# Spectacle_Motion_Board.net
KiCad netlist of a schematic drawn in EAGLE
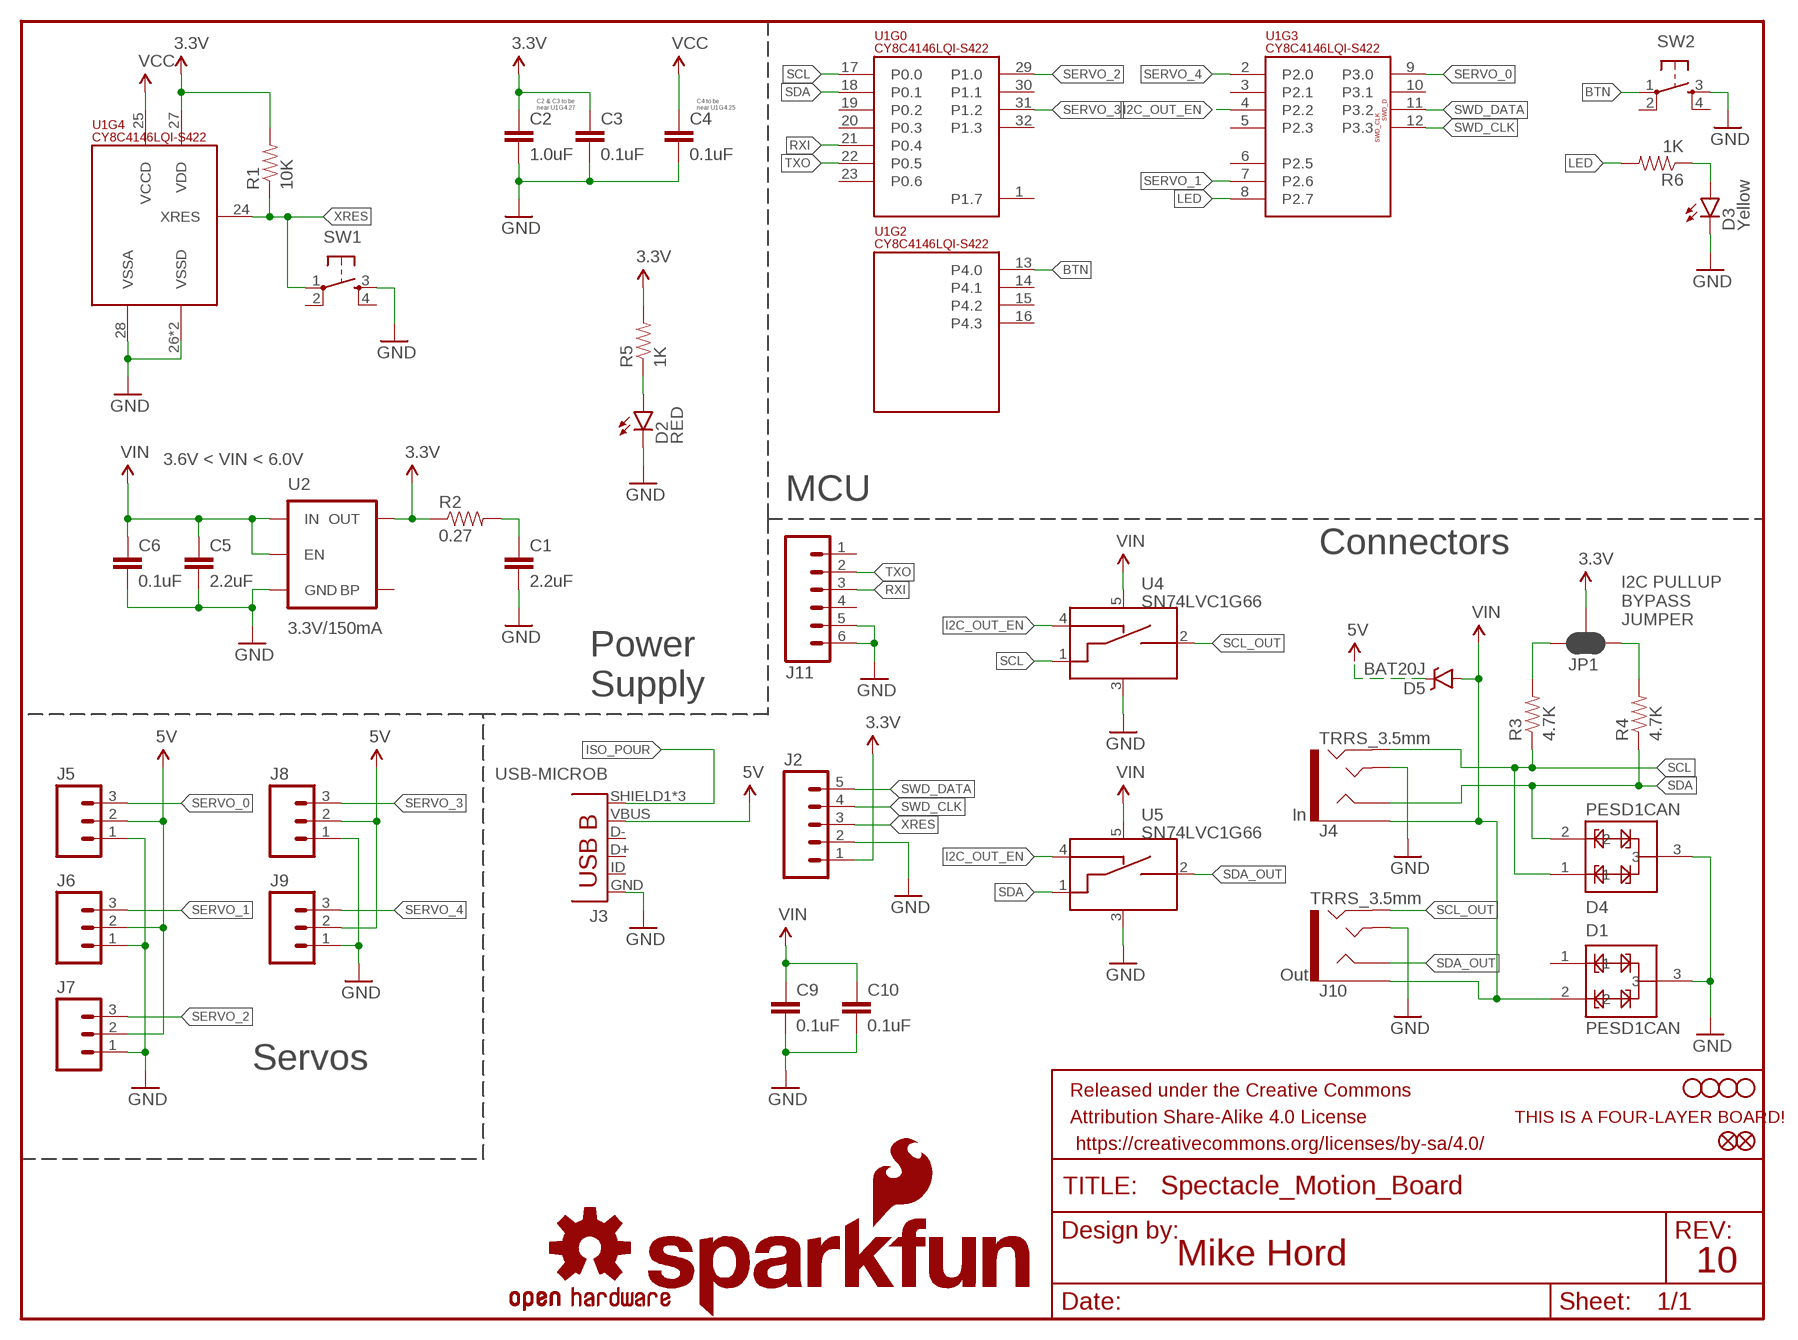
[diagram p0: schematic, sheet 1]

(export (version "E")
  (design (tool "Eeschema 10.0.6"))
  (components
    (comp (ref "C1")
      (value "2.2uF")
      (footprint "eagle-import:0603-CAP")
      (libsource (lib "eagle-import") (part "2.2UF-10V-20%(0603)"))
    )
    (comp (ref "C2")
      (value "1.0uF")
      (footprint "eagle-import:0402-CAP")
      (libsource (lib "eagle-import") (part "1.0UF-16V-10%(0402)"))
    )
    (comp (ref "C3")
      (value "0.1uF")
      (footprint "eagle-import:0402-CAP")
      (libsource (lib "eagle-import") (part "0.1UF-16V(+-10%)(0402)"))
    )
    (comp (ref "C4")
      (value "0.1uF")
      (footprint "eagle-import:0402-CAP")
      (libsource (lib "eagle-import") (part "0.1UF-16V(+-10%)(0402)"))
    )
    (comp (ref "C5")
      (value "2.2uF")
      (footprint "eagle-import:0603-CAP")
      (libsource (lib "eagle-import") (part "2.2UF-10V-20%(0603)"))
    )
    (comp (ref "C6")
      (value "0.1uF")
      (footprint "eagle-import:0402-CAP")
      (libsource (lib "eagle-import") (part "0.1UF-16V(+-10%)(0402)"))
    )
    (comp (ref "C9")
      (value "0.1uF")
      (footprint "eagle-import:0402-CAP")
      (libsource (lib "eagle-import") (part "0.1UF-16V(+-10%)(0402)"))
    )
    (comp (ref "C10")
      (value "0.1uF")
      (footprint "eagle-import:0402-CAP")
      (libsource (lib "eagle-import") (part "0.1UF-16V(+-10%)(0402)"))
    )
    (comp (ref "D1")
      (value "PESD1CAN")
      (footprint "eagle-import:SOT23-3")
      (libsource (lib "eagle-import") (part "PESD1CAN"))
    )
    (comp (ref "D2")
      (value "RED")
      (footprint "eagle-import:LED-0603")
      (libsource (lib "eagle-import") (part "LED-RED0603"))
    )
    (comp (ref "D3")
      (value "Yellow")
      (footprint "eagle-import:LED-0603")
      (libsource (lib "eagle-import") (part "LED-YELLOW0603-SMART"))
    )
    (comp (ref "D4")
      (value "PESD1CAN")
      (footprint "eagle-import:SOT23-3")
      (libsource (lib "eagle-import") (part "PESD1CAN"))
    )
    (comp (ref "D5")
      (value "BAT20J")
      (footprint "eagle-import:SOD-323")
      (libsource (lib "eagle-import") (part "DIODE-SCHOTTKY-BAT20J"))
    )
    (comp (ref "FD1")
      (value "FIDUCIALUFIDUCIAL")
      (footprint "eagle-import:MICRO-FIDUCIAL")
      (libsource (lib "eagle-import") (part "FIDUCIALUFIDUCIAL"))
    )
    (comp (ref "FD2")
      (value "FIDUCIALUFIDUCIAL")
      (footprint "eagle-import:MICRO-FIDUCIAL")
      (libsource (lib "eagle-import") (part "FIDUCIALUFIDUCIAL"))
    )
    (comp (ref "FRAME1")
      (value "FRAME-LETTER")
      (footprint "eagle-import:CREATIVE_COMMONS")
      (libsource (lib "eagle-import") (part "FRAME-LETTER"))
    )
    (comp (ref "H1")
      (value "STAND-OFF")
      (footprint "eagle-import:STAND-OFF")
      (libsource (lib "eagle-import") (part "STAND-OFF"))
    )
    (comp (ref "H2")
      (value "STAND-OFF")
      (footprint "eagle-import:STAND-OFF")
      (libsource (lib "eagle-import") (part "STAND-OFF"))
    )
    (comp (ref "H3")
      (value "STAND-OFF")
      (footprint "eagle-import:STAND-OFF")
      (libsource (lib "eagle-import") (part "STAND-OFF"))
    )
    (comp (ref "H4")
      (value "STAND-OFF")
      (footprint "eagle-import:STAND-OFF")
      (libsource (lib "eagle-import") (part "STAND-OFF"))
    )
    (comp (ref "J2")
      (value "M05NO_SILK")
      (footprint "eagle-import:1X05_NO_SILK")
      (libsource (lib "eagle-import") (part "M05NO_SILK"))
    )
    (comp (ref "J3")
      (value "USB-MICROB")
      (footprint "eagle-import:USB-B-MICRO-SMD_V03_RED_PASTE")
      (libsource (lib "eagle-import") (part "USB-MICROBREDUCED_PASTE"))
    )
    (comp (ref "J4")
      (value "TRRS_3.5mm")
      (footprint "eagle-import:AUDIO_JACK_3.5MM_TRRS_SMD_RA")
      (fields (field (name "PROD_ID") "CONN-10676"))
      (libsource (lib "eagle-import") (part "AUDIO_JACK_TRRSSMD_RA"))
    )
    (comp (ref "J5")
      (value "M03LOCK")
      (footprint "eagle-import:1X03_LOCK")
      (libsource (lib "eagle-import") (part "M03LOCK"))
    )
    (comp (ref "J6")
      (value "M03LOCK")
      (footprint "eagle-import:1X03_LOCK")
      (libsource (lib "eagle-import") (part "M03LOCK"))
    )
    (comp (ref "J7")
      (value "M03LOCK")
      (footprint "eagle-import:1X03_LOCK")
      (libsource (lib "eagle-import") (part "M03LOCK"))
    )
    (comp (ref "J8")
      (value "M03LOCK")
      (footprint "eagle-import:1X03_LOCK")
      (libsource (lib "eagle-import") (part "M03LOCK"))
    )
    (comp (ref "J9")
      (value "M03LOCK")
      (footprint "eagle-import:1X03_LOCK")
      (libsource (lib "eagle-import") (part "M03LOCK"))
    )
    (comp (ref "J10")
      (value "TRRS_3.5mm")
      (footprint "eagle-import:AUDIO_JACK_3.5MM_TRRS_SMD_RA")
      (fields (field (name "PROD_ID") "CONN-10676"))
      (libsource (lib "eagle-import") (part "AUDIO_JACK_TRRSSMD_RA"))
    )
    (comp (ref "J11")
      (value "M06NO_SILK_NO_POP")
      (footprint "eagle-import:1X06_NO_SILK")
      (libsource (lib "eagle-import") (part "M06NO_SILK_NO_POP"))
    )
    (comp (ref "JP1")
      (value "JUMPER-PAD-3-NC_BY_PASTE")
      (footprint "eagle-import:PAD-JUMPER-3-NC_BY_PASTE_YES_SILK_FULL_BOX")
      (libsource (lib "eagle-import") (part "JUMPER-PAD-3-NC_BY_PASTE"))
    )
    (comp (ref "LOGO1")
      (value "OSHW-LOGOS")
      (footprint "eagle-import:OSHW-LOGO-S")
      (libsource (lib "eagle-import") (part "OSHW-LOGOS"))
    )
    (comp (ref "LOGO2")
      (value "SFE_LOGO_NAME_FLAME.1_INCH")
      (footprint "eagle-import:SFE_LOGO_NAME_FLAME_.1")
      (libsource (lib "eagle-import") (part "SFE_LOGO_NAME_FLAME.1_INCH"))
    )
    (comp (ref "LOGO3")
      (value "SFE_LOGO_NAME_FLAME.1_INCH")
      (footprint "eagle-import:SFE_LOGO_NAME_FLAME_.1")
      (libsource (lib "eagle-import") (part "SFE_LOGO_NAME_FLAME.1_INCH"))
    )
    (comp (ref "LOGO4")
      (value "OSHW-LOGOS")
      (footprint "eagle-import:OSHW-LOGO-S")
      (libsource (lib "eagle-import") (part "OSHW-LOGOS"))
    )
    (comp (ref "R1")
      (value "10K")
      (footprint "eagle-import:0603-RES")
      (libsource (lib "eagle-import") (part "10KOHM-1/10W-1%(0603)0603"))
    )
    (comp (ref "R2")
      (value "0.27")
      (footprint "eagle-import:0603-RES")
      (libsource (lib "eagle-import") (part "0.27OHM-1/10W-1%(0603)"))
    )
    (comp (ref "R3")
      (value "4.7K")
      (footprint "eagle-import:0603-RES")
      (libsource (lib "eagle-import") (part "4.7KOHM-1/10W-1%(0603)"))
    )
    (comp (ref "R4")
      (value "4.7K")
      (footprint "eagle-import:0603-RES")
      (libsource (lib "eagle-import") (part "4.7KOHM-1/10W-1%(0603)"))
    )
    (comp (ref "R5")
      (value "1K")
      (footprint "eagle-import:0603-RES")
      (libsource (lib "eagle-import") (part "1KOHM-1/10W-1%(0603)"))
    )
    (comp (ref "R6")
      (value "1K")
      (footprint "eagle-import:0603-RES")
      (libsource (lib "eagle-import") (part "1KOHM-1/10W-1%(0603)"))
    )
    (comp (ref "SW1")
      (value "SWITCH_SPST_4_PINRECT")
      (footprint "eagle-import:TACTILE_SWITCH_SMD_4.6X2.8MM")
      (libsource (lib "eagle-import") (part "SWITCH_SPST_4_PINRECT"))
    )
    (comp (ref "SW2")
      (value "SWITCH_SPST_4_PINRECT")
      (footprint "eagle-import:TACTILE_SWITCH_SMD_4.6X2.8MM")
      (libsource (lib "eagle-import") (part "SWITCH_SPST_4_PINRECT"))
    )
    (comp (ref "U$1")
      (value "FOUR_LAYER_WARNING")
      (footprint "eagle-import:FOUR_LAYER_WARNING")
      (libsource (lib "eagle-import") (part "FOUR_LAYER_WARNING"))
    )
    (comp (ref "U1")
      (value "CY8C4146LQI-S422")
      (footprint "eagle-import:QFN-32")
      (libsource (lib "eagle-import") (part "PSOC4_4100S_32QFN"))
    )
    (comp (ref "U2")
      (value "3.3V/150mA")
      (footprint "eagle-import:SOT23-5")
      (libsource (lib "eagle-import") (part "V_REG_MIC52053.3V"))
    )
    (comp (ref "U4")
      (value "SN74LVC1G66")
      (footprint "eagle-import:SOT23-5")
      (libsource (lib "eagle-import") (part "SN74LVC1G66_SPST_AMUX"))
    )
    (comp (ref "U5")
      (value "SN74LVC1G66")
      (footprint "eagle-import:SOT23-5")
      (libsource (lib "eagle-import") (part "SN74LVC1G66_SPST_AMUX"))
    )
  )
  (nets
    (net (code "1") (name "3.3V") (class "Default")
      (node (ref "C2") (pin "1") (pinfunction "1_1") (pintype "passive"))
      (node (ref "C3") (pin "1") (pinfunction "1_1") (pintype "passive"))
      (node (ref "J2") (pin "1") (pinfunction "1_1") (pintype "passive"))
      (node (ref "JP1") (pin "2") (pinfunction "2_2") (pintype "passive"))
      (node (ref "R1") (pin "2") (pinfunction "2_2") (pintype "passive"))
      (node (ref "R2") (pin "1") (pinfunction "1_1") (pintype "passive"))
      (node (ref "R5") (pin "2") (pinfunction "2_2") (pintype "passive"))
      (node (ref "U1") (pin "27") (pinfunction "VDD_27") (pintype "bidirectional"))
      (node (ref "U2") (pin "5") (pinfunction "OUT_5") (pintype "passive"))
    )
    (net (code "2") (name "5V") (class "Default")
      (node (ref "D5") (pin "C") (pinfunction "C_C") (pintype "passive"))
      (node (ref "J3") (pin "VBUS") (pinfunction "VBUS_VBUS") (pintype "bidirectional"))
      (node (ref "J5") (pin "2") (pinfunction "2_2") (pintype "passive"))
      (node (ref "J6") (pin "2") (pinfunction "2_2") (pintype "passive"))
      (node (ref "J7") (pin "2") (pinfunction "2_2") (pintype "passive"))
      (node (ref "J8") (pin "2") (pinfunction "2_2") (pintype "passive"))
      (node (ref "J9") (pin "2") (pinfunction "2_2") (pintype "passive"))
    )
    (net (code "3") (name "BTN") (class "Default")
      (node (ref "SW2") (pin "1") (pinfunction "1_1") (pintype "passive"))
      (node (ref "U1") (pin "13") (pinfunction "P4.0_13") (pintype "bidirectional"))
    )
    (net (code "4") (name "GND") (class "Default")
      (node (ref "C1") (pin "2") (pinfunction "2_2") (pintype "passive"))
      (node (ref "C10") (pin "2") (pinfunction "2_2") (pintype "passive"))
      (node (ref "C2") (pin "2") (pinfunction "2_2") (pintype "passive"))
      (node (ref "C3") (pin "2") (pinfunction "2_2") (pintype "passive"))
      (node (ref "C4") (pin "2") (pinfunction "2_2") (pintype "passive"))
      (node (ref "C5") (pin "2") (pinfunction "2_2") (pintype "passive"))
      (node (ref "C6") (pin "2") (pinfunction "2_2") (pintype "passive"))
      (node (ref "C9") (pin "2") (pinfunction "2_2") (pintype "passive"))
      (node (ref "D1") (pin "3") (pinfunction "3_3") (pintype "bidirectional"))
      (node (ref "D2") (pin "C") (pinfunction "C_C") (pintype "passive"))
      (node (ref "D3") (pin "C") (pinfunction "C_C") (pintype "passive"))
      (node (ref "D4") (pin "3") (pinfunction "3_3") (pintype "bidirectional"))
      (node (ref "J10") (pin "TIP") (pinfunction "TIP_TIP") (pintype "bidirectional"))
      (node (ref "J11") (pin "5") (pinfunction "5_5") (pintype "passive"))
      (node (ref "J11") (pin "6") (pinfunction "6_6") (pintype "passive"))
      (node (ref "J2") (pin "2") (pinfunction "2_2") (pintype "passive"))
      (node (ref "J3") (pin "GND") (pinfunction "GND_GND") (pintype "bidirectional"))
      (node (ref "J4") (pin "TIP") (pinfunction "TIP_TIP") (pintype "bidirectional"))
      (node (ref "J5") (pin "1") (pinfunction "1_1") (pintype "passive"))
      (node (ref "J6") (pin "1") (pinfunction "1_1") (pintype "passive"))
      (node (ref "J7") (pin "1") (pinfunction "1_1") (pintype "passive"))
      (node (ref "J8") (pin "1") (pinfunction "1_1") (pintype "passive"))
      (node (ref "J9") (pin "1") (pinfunction "1_1") (pintype "passive"))
      (node (ref "SW1") (pin "3") (pinfunction "3_3") (pintype "passive"))
      (node (ref "SW2") (pin "3") (pinfunction "3_3") (pintype "passive"))
      (node (ref "U1") (pin "26") (pinfunction "VSSD_26") (pintype "bidirectional"))
      (node (ref "U1") (pin "28") (pinfunction "VSSA_28") (pintype "bidirectional"))
      (node (ref "U1") (pin "EP") (pinfunction "VSSD_EP") (pintype "bidirectional"))
      (node (ref "U2") (pin "2") (pinfunction "GND_2") (pintype "input"))
      (node (ref "U4") (pin "3") (pinfunction "VSS_3") (pintype "bidirectional"))
      (node (ref "U5") (pin "3") (pinfunction "VSS_3") (pintype "bidirectional"))
    )
    (net (code "5") (name "I2C_OUT_EN") (class "Default")
      (node (ref "U1") (pin "4") (pinfunction "P2.2_4") (pintype "bidirectional"))
      (node (ref "U4") (pin "4") (pinfunction "CTRL_IN_4") (pintype "bidirectional"))
      (node (ref "U5") (pin "4") (pinfunction "CTRL_IN_4") (pintype "bidirectional"))
    )
    (net (code "6") (name "ISO_POUR") (class "Default")
      (node (ref "J3") (pin "SHIELD1") (pinfunction "SHIELD_SHIELD1") (pintype "bidirectional"))
      (node (ref "J3") (pin "SHIELD2") (pinfunction "SHIELD_SHIELD2") (pintype "bidirectional"))
      (node (ref "J3") (pin "SHIELD3") (pinfunction "SHIELD_SHIELD3") (pintype "bidirectional"))
    )
    (net (code "7") (name "LED") (class "Default")
      (node (ref "R6") (pin "2") (pinfunction "2_2") (pintype "passive"))
      (node (ref "U1") (pin "8") (pinfunction "P2.7_8") (pintype "bidirectional"))
    )
    (net (code "8") (name "Net-(C1-Pad1)") (class "Default")
      (node (ref "C1") (pin "1") (pinfunction "1_1") (pintype "passive"))
      (node (ref "R2") (pin "2") (pinfunction "2_2") (pintype "passive"))
    )
    (net (code "9") (name "Net-(D2-PadA)") (class "Default")
      (node (ref "D2") (pin "A") (pinfunction "A_A") (pintype "passive"))
      (node (ref "R5") (pin "1") (pinfunction "1_1") (pintype "passive"))
    )
    (net (code "10") (name "Net-(D3-PadA)") (class "Default")
      (node (ref "D3") (pin "A") (pinfunction "A_A") (pintype "passive"))
      (node (ref "R6") (pin "1") (pinfunction "1_1") (pintype "passive"))
    )
    (net (code "11") (name "Net-(JP1-Pad1)") (class "Default")
      (node (ref "JP1") (pin "1") (pinfunction "1_1") (pintype "passive"))
      (node (ref "R4") (pin "2") (pinfunction "2_2") (pintype "passive"))
    )
    (net (code "12") (name "Net-(JP1-Pad3)") (class "Default")
      (node (ref "JP1") (pin "3") (pinfunction "3_3") (pintype "passive"))
      (node (ref "R3") (pin "2") (pinfunction "2_2") (pintype "passive"))
    )
    (net (code "13") (name "RXI") (class "Default")
      (node (ref "J11") (pin "3") (pinfunction "3_3") (pintype "passive"))
      (node (ref "U1") (pin "21") (pinfunction "P0.4_21") (pintype "bidirectional"))
    )
    (net (code "14") (name "SCL") (class "Default")
      (node (ref "D4") (pin "1") (pinfunction "1_1") (pintype "bidirectional"))
      (node (ref "J4") (pin "RING2") (pinfunction "RING2_RING2") (pintype "bidirectional"))
      (node (ref "R3") (pin "1") (pinfunction "1_1") (pintype "passive"))
      (node (ref "U1") (pin "17") (pinfunction "P0.0_17") (pintype "bidirectional"))
      (node (ref "U4") (pin "1") (pinfunction "A_IN_1") (pintype "bidirectional"))
    )
    (net (code "15") (name "SCL_OUT") (class "Default")
      (node (ref "J10") (pin "RING2") (pinfunction "RING2_RING2") (pintype "bidirectional"))
      (node (ref "U4") (pin "2") (pinfunction "A_OUT_2") (pintype "bidirectional"))
    )
    (net (code "16") (name "SDA") (class "Default")
      (node (ref "D4") (pin "2") (pinfunction "2_2") (pintype "bidirectional"))
      (node (ref "J4") (pin "RING1") (pinfunction "RING1_RING1") (pintype "bidirectional"))
      (node (ref "R4") (pin "1") (pinfunction "1_1") (pintype "passive"))
      (node (ref "U1") (pin "18") (pinfunction "P0.1_18") (pintype "bidirectional"))
      (node (ref "U5") (pin "1") (pinfunction "A_IN_1") (pintype "bidirectional"))
    )
    (net (code "17") (name "SDA_OUT") (class "Default")
      (node (ref "J10") (pin "RING1") (pinfunction "RING1_RING1") (pintype "bidirectional"))
      (node (ref "U5") (pin "2") (pinfunction "A_OUT_2") (pintype "bidirectional"))
    )
    (net (code "18") (name "SERVO_0") (class "Default")
      (node (ref "J5") (pin "3") (pinfunction "3_3") (pintype "passive"))
      (node (ref "U1") (pin "9") (pinfunction "P3.0_9") (pintype "bidirectional"))
    )
    (net (code "19") (name "SERVO_1") (class "Default")
      (node (ref "J6") (pin "3") (pinfunction "3_3") (pintype "passive"))
      (node (ref "U1") (pin "7") (pinfunction "P2.6_7") (pintype "bidirectional"))
    )
    (net (code "20") (name "SERVO_2") (class "Default")
      (node (ref "J7") (pin "3") (pinfunction "3_3") (pintype "passive"))
      (node (ref "U1") (pin "29") (pinfunction "P1.0_29") (pintype "bidirectional"))
    )
    (net (code "21") (name "SERVO_3") (class "Default")
      (node (ref "J8") (pin "3") (pinfunction "3_3") (pintype "passive"))
      (node (ref "U1") (pin "31") (pinfunction "P1.2_31") (pintype "bidirectional"))
    )
    (net (code "22") (name "SERVO_4") (class "Default")
      (node (ref "J9") (pin "3") (pinfunction "3_3") (pintype "passive"))
      (node (ref "U1") (pin "2") (pinfunction "P2.0_2") (pintype "bidirectional"))
    )
    (net (code "23") (name "SWD_CLK") (class "Default")
      (node (ref "J2") (pin "4") (pinfunction "4_4") (pintype "passive"))
      (node (ref "U1") (pin "12") (pinfunction "P3.3_12") (pintype "bidirectional"))
    )
    (net (code "24") (name "SWD_DATA") (class "Default")
      (node (ref "J2") (pin "5") (pinfunction "5_5") (pintype "passive"))
      (node (ref "U1") (pin "11") (pinfunction "P3.2_11") (pintype "bidirectional"))
    )
    (net (code "25") (name "TXO") (class "Default")
      (node (ref "J11") (pin "2") (pinfunction "2_2") (pintype "passive"))
      (node (ref "U1") (pin "22") (pinfunction "P0.5_22") (pintype "bidirectional"))
    )
    (net (code "26") (name "VCC") (class "Default")
      (node (ref "C4") (pin "1") (pinfunction "1_1") (pintype "passive"))
      (node (ref "U1") (pin "25") (pinfunction "VCCD_25") (pintype "bidirectional"))
    )
    (net (code "27") (name "VIN") (class "Default")
      (node (ref "C10") (pin "1") (pinfunction "1_1") (pintype "passive"))
      (node (ref "C5") (pin "1") (pinfunction "1_1") (pintype "passive"))
      (node (ref "C6") (pin "1") (pinfunction "1_1") (pintype "passive"))
      (node (ref "C9") (pin "1") (pinfunction "1_1") (pintype "passive"))
      (node (ref "D1") (pin "2") (pinfunction "2_2") (pintype "bidirectional"))
      (node (ref "D5") (pin "A") (pinfunction "A_A") (pintype "passive"))
      (node (ref "J10") (pin "EARTH") (pinfunction "EARTH_EARTH") (pintype "bidirectional"))
      (node (ref "J4") (pin "EARTH") (pinfunction "EARTH_EARTH") (pintype "bidirectional"))
      (node (ref "U2") (pin "1") (pinfunction "IN_1") (pintype "input"))
      (node (ref "U2") (pin "3") (pinfunction "EN_3") (pintype "input"))
      (node (ref "U4") (pin "5") (pinfunction "VCC_5") (pintype "bidirectional"))
      (node (ref "U5") (pin "5") (pinfunction "VCC_5") (pintype "bidirectional"))
    )
    (net (code "28") (name "XRES") (class "Default")
      (node (ref "J2") (pin "3") (pinfunction "3_3") (pintype "passive"))
      (node (ref "R1") (pin "1") (pinfunction "1_1") (pintype "passive"))
      (node (ref "SW1") (pin "1") (pinfunction "1_1") (pintype "passive"))
      (node (ref "U1") (pin "24") (pinfunction "XRES_24") (pintype "bidirectional"))
    )
    (net (code "29") (name "unconnected-(D1-Pad1)") (class "Default")
      (node (ref "D1") (pin "1") (pinfunction "1_1") (pintype "bidirectional"))
    )
    (net (code "30") (name "unconnected-(J3-PadD+)") (class "Default")
      (node (ref "J3") (pin "D+") (pinfunction "D+_D+") (pintype "bidirectional"))
    )
    (net (code "31") (name "unconnected-(J3-PadD-)") (class "Default")
      (node (ref "J3") (pin "D-") (pinfunction "D-_D-") (pintype "bidirectional"))
    )
    (net (code "32") (name "unconnected-(J3-USBID-PadID)") (class "Default")
      (node (ref "J3") (pin "ID") (pinfunction "USBID_ID") (pintype "bidirectional"))
    )
    (net (code "33") (name "unconnected-(J11-Pad1)") (class "Default")
      (node (ref "J11") (pin "1") (pinfunction "1_1") (pintype "passive"))
    )
    (net (code "34") (name "unconnected-(J11-Pad4)") (class "Default")
      (node (ref "J11") (pin "4") (pinfunction "4_4") (pintype "passive"))
    )
    (net (code "35") (name "unconnected-(SW1-Pad2)") (class "Default")
      (node (ref "SW1") (pin "2") (pinfunction "2_2") (pintype "passive"))
    )
    (net (code "36") (name "unconnected-(SW1-Pad4)") (class "Default")
      (node (ref "SW1") (pin "4") (pinfunction "4_4") (pintype "passive"))
    )
    (net (code "37") (name "unconnected-(SW2-Pad2)") (class "Default")
      (node (ref "SW2") (pin "2") (pinfunction "2_2") (pintype "passive"))
    )
    (net (code "38") (name "unconnected-(SW2-Pad4)") (class "Default")
      (node (ref "SW2") (pin "4") (pinfunction "4_4") (pintype "passive"))
    )
    (net (code "39") (name "unconnected-(U1A-P0.2-Pad19)") (class "Default")
      (node (ref "U1") (pin "19") (pinfunction "P0.2_19") (pintype "bidirectional"))
    )
    (net (code "40") (name "unconnected-(U1A-P0.3-Pad20)") (class "Default")
      (node (ref "U1") (pin "20") (pinfunction "P0.3_20") (pintype "bidirectional"))
    )
    (net (code "41") (name "unconnected-(U1A-P0.6-Pad23)") (class "Default")
      (node (ref "U1") (pin "23") (pinfunction "P0.6_23") (pintype "bidirectional"))
    )
    (net (code "42") (name "unconnected-(U1A-P1.1-Pad30)") (class "Default")
      (node (ref "U1") (pin "30") (pinfunction "P1.1_30") (pintype "bidirectional"))
    )
    (net (code "43") (name "unconnected-(U1A-P1.3-Pad32)") (class "Default")
      (node (ref "U1") (pin "32") (pinfunction "P1.3_32") (pintype "bidirectional"))
    )
    (net (code "44") (name "unconnected-(U1A-P1.7-Pad1)") (class "Default")
      (node (ref "U1") (pin "1") (pinfunction "P1.7_1") (pintype "bidirectional"))
    )
    (net (code "45") (name "unconnected-(U1B-P4.1-Pad14)") (class "Default")
      (node (ref "U1") (pin "14") (pinfunction "P4.1_14") (pintype "bidirectional"))
    )
    (net (code "46") (name "unconnected-(U1B-P4.2-Pad15)") (class "Default")
      (node (ref "U1") (pin "15") (pinfunction "P4.2_15") (pintype "bidirectional"))
    )
    (net (code "47") (name "unconnected-(U1B-P4.3-Pad16)") (class "Default")
      (node (ref "U1") (pin "16") (pinfunction "P4.3_16") (pintype "bidirectional"))
    )
    (net (code "48") (name "unconnected-(U1C-P2.1-Pad3)") (class "Default")
      (node (ref "U1") (pin "3") (pinfunction "P2.1_3") (pintype "bidirectional"))
    )
    (net (code "49") (name "unconnected-(U1C-P2.3-Pad5)") (class "Default")
      (node (ref "U1") (pin "5") (pinfunction "P2.3_5") (pintype "bidirectional"))
    )
    (net (code "50") (name "unconnected-(U1C-P2.5-Pad6)") (class "Default")
      (node (ref "U1") (pin "6") (pinfunction "P2.5_6") (pintype "bidirectional"))
    )
    (net (code "51") (name "unconnected-(U1C-P3.1-Pad10)") (class "Default")
      (node (ref "U1") (pin "10") (pinfunction "P3.1_10") (pintype "bidirectional"))
    )
    (net (code "52") (name "unconnected-(U2-BP-Pad4)") (class "Default")
      (node (ref "U2") (pin "4") (pinfunction "BP_4") (pintype "input"))
    )
  )
)
